# educationalBoard.net
KiCad netlist of a schematic drawn in Altium Designer
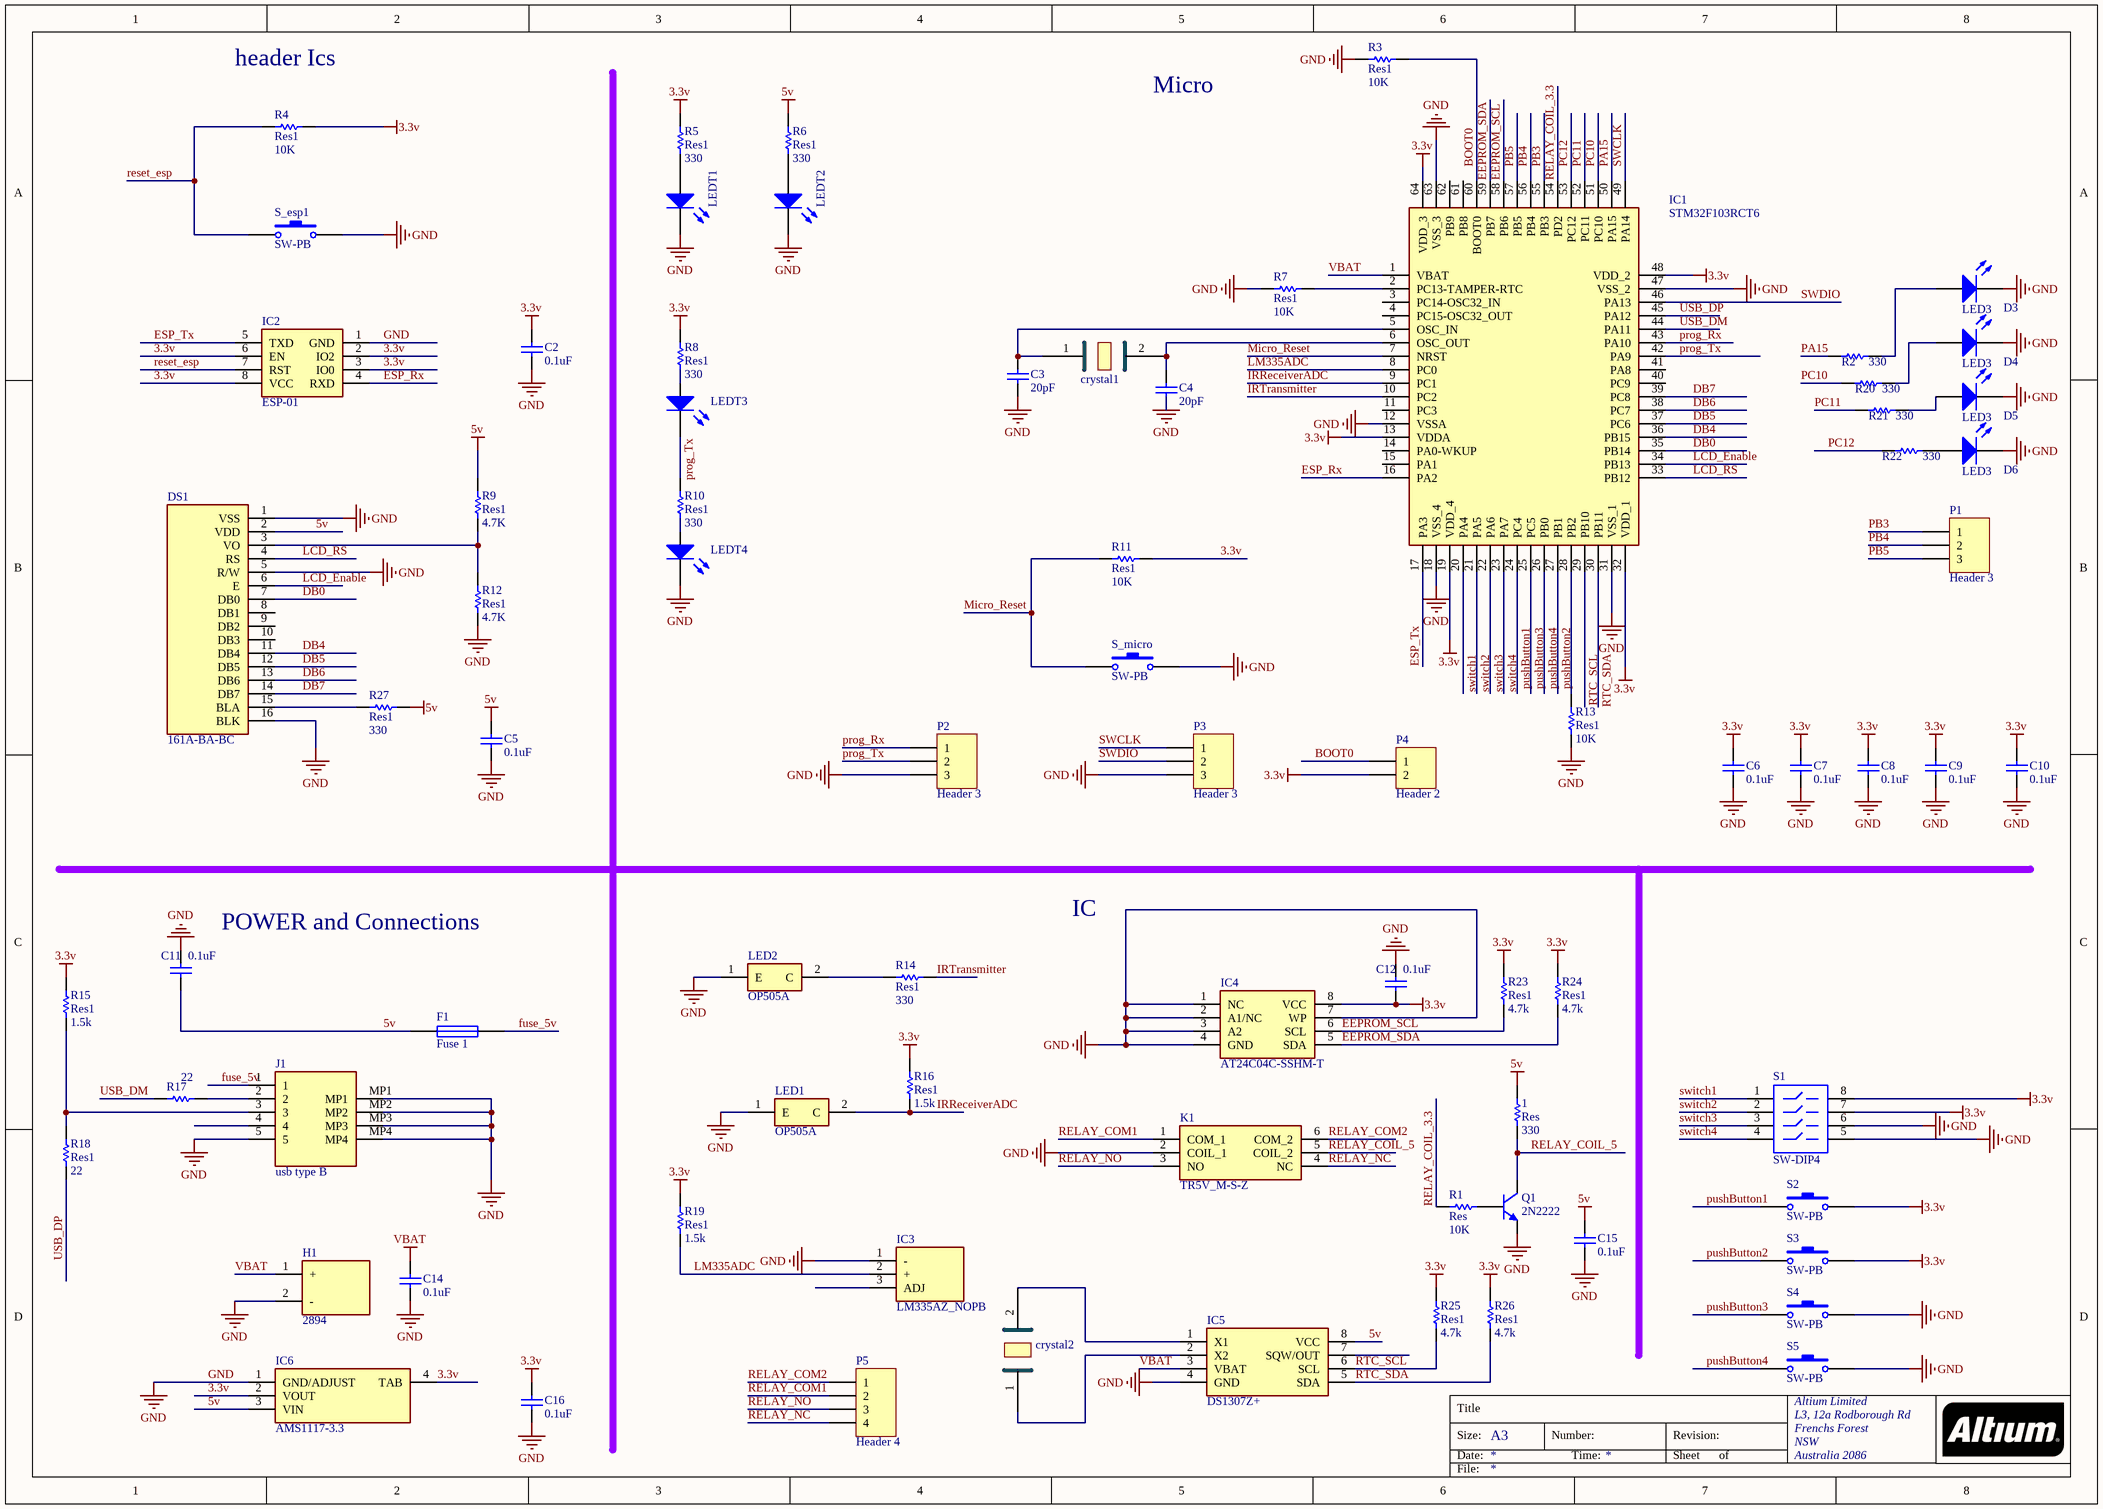
[diagram p0: educationalBoard.SchDoc]

(export (version "E")
  (design (tool "Eeschema 10.0.6"))
  (components
    (comp (ref "1")
      (value "Res")
      (footprint "J1-0603")
      (description "Semiconductor Resistor")
      (fields (field (name "ALTIUM_VALUE") "330") (field (name "PUBLISHER") "Altium Limited"))
      (libsource (lib "KN2CLib") (part "Res"))
    )
    (comp (ref "C2")
      (value "0.1uF")
      (footprint "J1-0603")
      (description "Ceramic Chip Capacitor - Standard")
      (fields (field (name "Comment") "C0603") (field (name "PUBLISHER") "Altium Limited"))
      (libsource (lib "KEMET Chip Capacitor") (part "C0603"))
    )
    (comp (ref "C3")
      (value "20pF")
      (footprint "J1-0603")
      (description "Ceramic Chip Capacitor - Standard")
      (fields (field (name "Comment") "C0603") (field (name "PUBLISHER") "Altium Limited"))
      (libsource (lib "KEMET Chip Capacitor") (part "C0603"))
    )
    (comp (ref "C4")
      (value "20pF")
      (footprint "J1-0603")
      (description "Ceramic Chip Capacitor - Standard")
      (fields (field (name "Comment") "C0603") (field (name "PUBLISHER") "Altium Limited"))
      (libsource (lib "KEMET Chip Capacitor") (part "C0603"))
    )
    (comp (ref "C5")
      (value "0.1uF")
      (footprint "J1-0603")
      (description "Ceramic Chip Capacitor - Standard")
      (fields (field (name "Comment") "C0603") (field (name "PUBLISHER") "Altium Limited"))
      (libsource (lib "KEMET Chip Capacitor") (part "C0603"))
    )
    (comp (ref "C6")
      (value "0.1uF")
      (footprint "J1-0603")
      (description "Ceramic Chip Capacitor - Standard")
      (fields (field (name "Comment") "C0603") (field (name "PUBLISHER") "Altium Limited"))
      (libsource (lib "KEMET Chip Capacitor") (part "C0603"))
    )
    (comp (ref "C7")
      (value "0.1uF")
      (footprint "J1-0603")
      (description "Ceramic Chip Capacitor - Standard")
      (fields (field (name "Comment") "C0603") (field (name "PUBLISHER") "Altium Limited"))
      (libsource (lib "KEMET Chip Capacitor") (part "C0603"))
    )
    (comp (ref "C8")
      (value "0.1uF")
      (footprint "J1-0603")
      (description "Ceramic Chip Capacitor - Standard")
      (fields (field (name "Comment") "C0603") (field (name "PUBLISHER") "Altium Limited"))
      (libsource (lib "KEMET Chip Capacitor") (part "C0603"))
    )
    (comp (ref "C9")
      (value "0.1uF")
      (footprint "J1-0603")
      (description "Ceramic Chip Capacitor - Standard")
      (fields (field (name "Comment") "C0603") (field (name "PUBLISHER") "Altium Limited"))
      (libsource (lib "KEMET Chip Capacitor") (part "C0603"))
    )
    (comp (ref "C10")
      (value "0.1uF")
      (footprint "J1-0603")
      (description "Ceramic Chip Capacitor - Standard")
      (fields (field (name "Comment") "C0603") (field (name "PUBLISHER") "Altium Limited"))
      (libsource (lib "KEMET Chip Capacitor") (part "C0603"))
    )
    (comp (ref "C11")
      (value "0.1uF")
      (footprint "J1-0603")
      (description "Ceramic Chip Capacitor - Standard")
      (fields (field (name "Comment") "C0603") (field (name "PUBLISHER") "Altium Limited"))
      (libsource (lib "KEMET Chip Capacitor") (part "C0603"))
    )
    (comp (ref "C12")
      (value "0.1uF")
      (footprint "J1-0603")
      (description "Ceramic Chip Capacitor - Standard")
      (fields (field (name "Comment") "C0603") (field (name "PUBLISHER") "Altium Limited"))
      (libsource (lib "KEMET Chip Capacitor") (part "C0603"))
    )
    (comp (ref "C14")
      (value "0.1uF")
      (footprint "J1-0603")
      (description "Ceramic Chip Capacitor - Standard")
      (fields (field (name "Comment") "C0603") (field (name "PUBLISHER") "Altium Limited"))
      (libsource (lib "KEMET Chip Capacitor") (part "C0603"))
    )
    (comp (ref "C15")
      (value "0.1uF")
      (footprint "J1-0603")
      (description "Ceramic Chip Capacitor - Standard")
      (fields (field (name "Comment") "C0603") (field (name "PUBLISHER") "Altium Limited"))
      (libsource (lib "KEMET Chip Capacitor") (part "C0603"))
    )
    (comp (ref "C16")
      (value "0.1uF")
      (footprint "J1-0603")
      (description "Ceramic Chip Capacitor - Standard")
      (fields (field (name "Comment") "C0603") (field (name "PUBLISHER") "Altium Limited"))
      (libsource (lib "KEMET Chip Capacitor") (part "C0603"))
    )
    (comp (ref "crystal1")
      (value "clockProducerDeep")
      (footprint "deep crystal")
      (libsource (lib "Schlib1") (part "deep crystal"))
    )
    (comp (ref "crystal2")
      (value "clockProducerDeep")
      (footprint "Deep Crystal small")
      (libsource (lib "") (part "deep crystal_1"))
    )
    (comp (ref "D3")
      (value "LED3")
      (footprint "3518")
      (description "Typical BLUE SiC LED")
      (fields (field (name "PUBLISHER") "Altium Limited"))
      (libsource (lib "Miscellaneous Devices") (part "LED3"))
    )
    (comp (ref "D4")
      (value "LED3")
      (footprint "3518")
      (description "Typical BLUE SiC LED")
      (fields (field (name "PUBLISHER") "Altium Limited"))
      (libsource (lib "Miscellaneous Devices") (part "LED3"))
    )
    (comp (ref "D5")
      (value "LED3")
      (footprint "3518")
      (description "Typical BLUE SiC LED")
      (fields (field (name "PUBLISHER") "Altium Limited"))
      (libsource (lib "Miscellaneous Devices") (part "LED3"))
    )
    (comp (ref "D6")
      (value "LED3")
      (footprint "3518")
      (description "Typical BLUE SiC LED")
      (fields (field (name "PUBLISHER") "Altium Limited"))
      (libsource (lib "Miscellaneous Devices") (part "LED3"))
    )
    (comp (ref "DS1")
      (value "161A-BA-BC")
      (footprint "Miscellaneous Connectors:HDR1X16")
      (description "Display")
      (libsource (lib "SamacSys") (part "161A-BA-BC"))
    )
    (comp (ref "F1")
      (value "Fuse 1")
      (footprint "0805")
      (description "Fuse")
      (fields (field (name "PUBLISHER") "Altium Limited"))
      (libsource (lib "Miscellaneous Devices") (part "Fuse 1"))
    )
    (comp (ref "H1")
      (value "2894")
      (footprint "SamacSys:2894")
      (description "Hardware")
      (fields (field (name "MOUSER PART NUMBER") "534-2894"))
      (libsource (lib "SamacSys") (part "2894"))
    )
    (comp (ref "IC1")
      (value "STM32F103RCT6")
      (footprint "SamacSys:QFP50P1200X1200X160-64N")
      (description "Integrated Circuit")
      (fields (field (name "MOUSER PART NUMBER") "511-STM32F103RCT6"))
      (libsource (lib "*") (part "STM32F103RCT6"))
    )
    (comp (ref "IC2")
      (value "ESP-01")
      (footprint "HDR2X4")
      (description "Integrated Circuit")
      (libsource (lib "*") (part "ESP-01"))
    )
    (comp (ref "IC3")
      (value "LM335AZ_NOPB")
      (footprint "HDR1X3")
      (description "Integrated Circuit")
      (fields
        (field (name "MANUFACTURER_PART_NUMBER") "LM335AZ/NOPB")
        (field (name "MOUSER PART NUMBER") "926-LM335AZ/NOPB")
      )
      (libsource (lib "*") (part "LM335AZ_NOPB"))
    )
    (comp (ref "IC4")
      (value "AT24C04C-SSHM-T")
      (footprint "SamacSys:SOIC127P600X175-8N")
      (description "Integrated Circuit")
      (fields (field (name "MOUSER PART NUMBER") "556-AT24C04C-SSHM-T"))
      (libsource (lib "*") (part "AT24C04C-SSHM-T"))
    )
    (comp (ref "IC5")
      (value "DS1307Z+")
      (footprint "SamacSys:SOIC127P600X175-8N")
      (description "Integrated Circuit")
      (fields (field (name "MOUSER PART NUMBER") "700-DS1307Z"))
      (libsource (lib "*") (part "DS1307Z+"))
    )
    (comp (ref "IC6")
      (value "AMS1117-3.3")
      (footprint "SamacSys:SOT229P700X180-4N")
      (description "Integrated Circuit")
      (fields (field (name "MANUFACTURER_PART_NUMBER") "AMS1117-1.5"))
      (libsource (lib "*") (part "AMS1117-1.5"))
    )
    (comp (ref "J1")
      (value "usb type B")
      (footprint "SamacSys:0474910001")
      (description "Connector")
      (fields (field (name "MANUFACTURER_PART_NUMBER") "0474910001"))
      (libsource (lib "SamacSys") (part "0474910001"))
    )
    (comp (ref "K1")
      (value "TR5V_M-S-Z")
      (footprint "SamacSys:TR5VMSZ")
      (description "Relay or Contactor")
      (fields (field (name "MANUFACTURER_PART_NUMBER") "TR5V M-S-Z"))
      (libsource (lib "*") (part "TR5V_M-S-Z"))
    )
    (comp (ref "LED1")
      (value "OP505A")
      (footprint "SamacSys:OP505A")
      (description "LED (Multiple)")
      (fields (field (name "MOUSER PART NUMBER") "828-OP505A"))
      (libsource (lib "SamacSys") (part "OP505A"))
    )
    (comp (ref "LED2")
      (value "OP505A")
      (footprint "SamacSys:OP505A")
      (description "LED (Multiple)")
      (fields (field (name "MOUSER PART NUMBER") "828-OP505A"))
      (libsource (lib "SamacSys") (part "OP505A"))
    )
    (comp (ref "LEDT1")
      (value "~")
      (footprint "3518")
      (description "Typical BLUE SiC LED")
      (fields (field (name "PUBLISHER") "Altium Limited"))
      (libsource (lib "Miscellaneous Devices") (part "LED3"))
    )
    (comp (ref "LEDT2")
      (value "~")
      (footprint "3518")
      (description "Typical BLUE SiC LED")
      (fields (field (name "PUBLISHER") "Altium Limited"))
      (libsource (lib "Miscellaneous Devices") (part "LED3"))
    )
    (comp (ref "LEDT3")
      (value "~")
      (footprint "3518")
      (description "Typical BLUE SiC LED")
      (fields (field (name "PUBLISHER") "Altium Limited"))
      (libsource (lib "Miscellaneous Devices") (part "LED3"))
    )
    (comp (ref "LEDT4")
      (value "~")
      (footprint "3518")
      (description "Typical BLUE SiC LED")
      (fields (field (name "PUBLISHER") "Altium Limited"))
      (libsource (lib "Miscellaneous Devices") (part "LED3"))
    )
    (comp (ref "P1")
      (value "Header 3")
      (footprint "HDR1X3")
      (description "Header, 3-Pin")
      (fields (field (name "PUBLISHER") "Altium Limited"))
      (libsource (lib "Miscellaneous Connectors") (part "Header 3"))
    )
    (comp (ref "P2")
      (value "Header 3")
      (footprint "HDR1X3")
      (description "Header, 3-Pin")
      (fields (field (name "PUBLISHER") "Altium Limited"))
      (libsource (lib "Miscellaneous Connectors") (part "Header 3"))
    )
    (comp (ref "P3")
      (value "Header 3")
      (footprint "HDR1X3")
      (description "Header, 3-Pin")
      (fields (field (name "PUBLISHER") "Altium Limited"))
      (libsource (lib "Miscellaneous Connectors") (part "Header 3"))
    )
    (comp (ref "P4")
      (value "Header 2")
      (footprint "HDR1X2")
      (description "Header, 2-Pin")
      (fields (field (name "PUBLISHER") "Altium Limited"))
      (libsource (lib "Miscellaneous Connectors") (part "Header 2"))
    )
    (comp (ref "P5")
      (value "Header 4")
      (footprint "HDR1X4")
      (description "Header, 4-Pin")
      (fields (field (name "PUBLISHER") "Altium Limited"))
      (libsource (lib "Miscellaneous Connectors") (part "Header 4"))
    )
    (comp (ref "Q1")
      (value "2N2222")
      (footprint "SOT-23")
      (description "NPN Bipolar Transistor")
      (fields (field (name "PUBLISHER") "Altium Limited"))
      (libsource (lib "KN2CLib") (part "2N2222"))
    )
    (comp (ref "R1")
      (value "Res")
      (footprint "J1-0603")
      (description "Semiconductor Resistor")
      (fields (field (name "ALTIUM_VALUE") "10K") (field (name "PUBLISHER") "Altium Limited"))
      (libsource (lib "KN2CLib") (part "Res"))
    )
    (comp (ref "R2")
      (value "330")
      (footprint "j1-0603")
      (description "Resistor")
      (fields (field (name "Comment") "Res1") (field (name "PUBLISHER") "Altium Limited"))
      (libsource (lib "Miscellaneous Devices") (part "Res1"))
    )
    (comp (ref "R3")
      (value "Res1")
      (footprint "J1-0603")
      (description "Resistor")
      (fields (field (name "ALTIUM_VALUE") "10K") (field (name "PUBLISHER") "Altium Limited"))
      (libsource (lib "Miscellaneous Devices") (part "Res1"))
    )
    (comp (ref "R4")
      (value "Res1")
      (footprint "J1-0603")
      (description "Resistor")
      (fields (field (name "ALTIUM_VALUE") "10K") (field (name "PUBLISHER") "Altium Limited"))
      (libsource (lib "Miscellaneous Devices") (part "Res1"))
    )
    (comp (ref "R5")
      (value "Res1")
      (footprint "j1-0603")
      (description "Resistor")
      (fields (field (name "ALTIUM_VALUE") "330") (field (name "PUBLISHER") "Altium Limited"))
      (libsource (lib "Miscellaneous Devices") (part "Res1"))
    )
    (comp (ref "R6")
      (value "Res1")
      (footprint "j1-0603")
      (description "Resistor")
      (fields (field (name "ALTIUM_VALUE") "330") (field (name "PUBLISHER") "Altium Limited"))
      (libsource (lib "Miscellaneous Devices") (part "Res1"))
    )
    (comp (ref "R7")
      (value "Res1")
      (footprint "J1-0603")
      (description "Resistor")
      (fields (field (name "ALTIUM_VALUE") "10K") (field (name "PUBLISHER") "Altium Limited"))
      (libsource (lib "Miscellaneous Devices") (part "Res1"))
    )
    (comp (ref "R8")
      (value "Res1")
      (footprint "j1-0603")
      (description "Resistor")
      (fields (field (name "ALTIUM_VALUE") "330") (field (name "PUBLISHER") "Altium Limited"))
      (libsource (lib "Miscellaneous Devices") (part "Res1"))
    )
    (comp (ref "R9")
      (value "Res1")
      (footprint "J1-0603")
      (description "Resistor")
      (fields (field (name "ALTIUM_VALUE") "4.7K") (field (name "PUBLISHER") "Altium Limited"))
      (libsource (lib "Miscellaneous Devices") (part "Res1"))
    )
    (comp (ref "R10")
      (value "Res1")
      (footprint "j1-0603")
      (description "Resistor")
      (fields (field (name "ALTIUM_VALUE") "330") (field (name "PUBLISHER") "Altium Limited"))
      (libsource (lib "Miscellaneous Devices") (part "Res1"))
    )
    (comp (ref "R11")
      (value "Res1")
      (footprint "J1-0603")
      (description "Resistor")
      (fields (field (name "ALTIUM_VALUE") "10K") (field (name "PUBLISHER") "Altium Limited"))
      (libsource (lib "Miscellaneous Devices") (part "Res1"))
    )
    (comp (ref "R12")
      (value "Res1")
      (footprint "J1-0603")
      (description "Resistor")
      (fields (field (name "ALTIUM_VALUE") "4.7K") (field (name "PUBLISHER") "Altium Limited"))
      (libsource (lib "Miscellaneous Devices") (part "Res1"))
    )
    (comp (ref "R13")
      (value "Res1")
      (footprint "J1-0603")
      (description "Resistor")
      (fields (field (name "ALTIUM_VALUE") "10K") (field (name "PUBLISHER") "Altium Limited"))
      (libsource (lib "Miscellaneous Devices") (part "Res1"))
    )
    (comp (ref "R14")
      (value "Res1")
      (footprint "J1-0603")
      (description "Resistor")
      (fields (field (name "ALTIUM_VALUE") "330") (field (name "PUBLISHER") "Altium Limited"))
      (libsource (lib "Miscellaneous Devices") (part "Res1"))
    )
    (comp (ref "R15")
      (value "Res1")
      (footprint "J1-0603")
      (description "Resistor")
      (fields (field (name "ALTIUM_VALUE") "1.5k") (field (name "PUBLISHER") "Altium Limited"))
      (libsource (lib "Miscellaneous Devices") (part "Res1"))
    )
    (comp (ref "R16")
      (value "Res1")
      (footprint "J1-0603")
      (description "Resistor")
      (fields (field (name "ALTIUM_VALUE") "1.5k") (field (name "PUBLISHER") "Altium Limited"))
      (libsource (lib "Miscellaneous Devices") (part "Res1"))
    )
    (comp (ref "R17")
      (value "22")
      (footprint "J1-0603")
      (description "Resistor")
      (fields (field (name "Comment") "Res1") (field (name "PUBLISHER") "Altium Limited"))
      (libsource (lib "Miscellaneous Devices") (part "Res1"))
    )
    (comp (ref "R18")
      (value "Res1")
      (footprint "J1-0603")
      (description "Resistor")
      (fields (field (name "ALTIUM_VALUE") "22") (field (name "PUBLISHER") "Altium Limited"))
      (libsource (lib "Miscellaneous Devices") (part "Res1"))
    )
    (comp (ref "R19")
      (value "Res1")
      (footprint "J1-0603")
      (description "Resistor")
      (fields (field (name "ALTIUM_VALUE") "1.5k") (field (name "PUBLISHER") "Altium Limited"))
      (libsource (lib "Miscellaneous Devices") (part "Res1"))
    )
    (comp (ref "R20")
      (value "330")
      (footprint "j1-0603")
      (description "Resistor")
      (fields (field (name "Comment") "Res1") (field (name "PUBLISHER") "Altium Limited"))
      (libsource (lib "Miscellaneous Devices") (part "Res1"))
    )
    (comp (ref "R21")
      (value "330")
      (footprint "j1-0603")
      (description "Resistor")
      (fields (field (name "Comment") "Res1") (field (name "PUBLISHER") "Altium Limited"))
      (libsource (lib "Miscellaneous Devices") (part "Res1"))
    )
    (comp (ref "R22")
      (value "330")
      (footprint "j1-0603")
      (description "Resistor")
      (fields (field (name "Comment") "Res1") (field (name "PUBLISHER") "Altium Limited"))
      (libsource (lib "Miscellaneous Devices") (part "Res1"))
    )
    (comp (ref "R23")
      (value "Res1")
      (footprint "J1-0603")
      (description "Resistor")
      (fields (field (name "ALTIUM_VALUE") "4.7k") (field (name "PUBLISHER") "Altium Limited"))
      (libsource (lib "Miscellaneous Devices") (part "Res1"))
    )
    (comp (ref "R24")
      (value "Res1")
      (footprint "J1-0603")
      (description "Resistor")
      (fields (field (name "ALTIUM_VALUE") "4.7k") (field (name "PUBLISHER") "Altium Limited"))
      (libsource (lib "Miscellaneous Devices") (part "Res1"))
    )
    (comp (ref "R25")
      (value "Res1")
      (footprint "J1-0603")
      (description "Resistor")
      (fields (field (name "ALTIUM_VALUE") "4.7k") (field (name "PUBLISHER") "Altium Limited"))
      (libsource (lib "Miscellaneous Devices") (part "Res1"))
    )
    (comp (ref "R26")
      (value "Res1")
      (footprint "J1-0603")
      (description "Resistor")
      (fields (field (name "ALTIUM_VALUE") "4.7k") (field (name "PUBLISHER") "Altium Limited"))
      (libsource (lib "Miscellaneous Devices") (part "Res1"))
    )
    (comp (ref "R27")
      (value "Res1")
      (footprint "J1-0603")
      (description "Resistor")
      (fields (field (name "ALTIUM_VALUE") "330") (field (name "PUBLISHER") "Altium Limited"))
      (libsource (lib "Miscellaneous Devices") (part "Res1"))
    )
    (comp (ref "S1")
      (value "SW-DIP4")
      (footprint "DIP-8")
      (description "DIP Switch")
      (fields (field (name "PUBLISHER") "Altium Limited"))
      (libsource (lib "Miscellaneous Devices") (part "SW-DIP4"))
    )
    (comp (ref "S2")
      (value "SW-PB")
      (footprint "button")
      (description "Switch")
      (fields (field (name "PUBLISHER") "Altium Limited"))
      (libsource (lib "Miscellaneous Devices") (part "SW-PB"))
    )
    (comp (ref "S3")
      (value "SW-PB")
      (footprint "button")
      (description "Switch")
      (fields (field (name "PUBLISHER") "Altium Limited"))
      (libsource (lib "Miscellaneous Devices") (part "SW-PB"))
    )
    (comp (ref "S4")
      (value "SW-PB")
      (footprint "button")
      (description "Switch")
      (fields (field (name "PUBLISHER") "Altium Limited"))
      (libsource (lib "Miscellaneous Devices") (part "SW-PB"))
    )
    (comp (ref "S5")
      (value "SW-PB")
      (footprint "button")
      (description "Switch")
      (fields (field (name "PUBLISHER") "Altium Limited"))
      (libsource (lib "Miscellaneous Devices") (part "SW-PB"))
    )
    (comp (ref "S_esp1")
      (value "SW-PB")
      (footprint "button")
      (description "Switch")
      (fields (field (name "PUBLISHER") "Altium Limited"))
      (libsource (lib "Miscellaneous Devices") (part "SW-PB"))
    )
    (comp (ref "S_micro")
      (value "SW-PB")
      (footprint "button")
      (description "Switch")
      (fields (field (name "PUBLISHER") "Altium Limited"))
      (libsource (lib "Miscellaneous Devices") (part "SW-PB"))
    )
  )
  (nets
    (net (code "1") (name "/BOOT0") (class "Default")
      (node (ref "IC1") (pin "60") (pinfunction "BOOT0_60") (pintype "passive"))
      (node (ref "P4") (pin "1") (pinfunction "1_1") (pintype "passive"))
      (node (ref "R3") (pin "1") (pinfunction "1_1") (pintype "passive"))
    )
    (net (code "2") (name "/DB0") (class "Default")
      (node (ref "DS1") (pin "7") (pinfunction "DB0_7") (pintype "passive"))
      (node (ref "IC1") (pin "35") (pinfunction "PB14_35") (pintype "passive"))
    )
    (net (code "3") (name "/DB4") (class "Default")
      (node (ref "DS1") (pin "11") (pinfunction "DB4_11") (pintype "passive"))
      (node (ref "IC1") (pin "36") (pinfunction "PB15_36") (pintype "passive"))
    )
    (net (code "4") (name "/DB5") (class "Default")
      (node (ref "DS1") (pin "12") (pinfunction "DB5_12") (pintype "passive"))
      (node (ref "IC1") (pin "37") (pinfunction "PC6_37") (pintype "passive"))
    )
    (net (code "5") (name "/DB6") (class "Default")
      (node (ref "DS1") (pin "13") (pinfunction "DB6_13") (pintype "passive"))
      (node (ref "IC1") (pin "38") (pinfunction "PC7_38") (pintype "passive"))
    )
    (net (code "6") (name "/DB7") (class "Default")
      (node (ref "DS1") (pin "14") (pinfunction "DB7_14") (pintype "passive"))
      (node (ref "IC1") (pin "39") (pinfunction "PC8_39") (pintype "passive"))
    )
    (net (code "7") (name "/EEPROM_SCL") (class "Default")
      (node (ref "IC1") (pin "58") (pinfunction "PB6_58") (pintype "passive"))
      (node (ref "IC4") (pin "6") (pinfunction "SCL_6") (pintype "passive"))
      (node (ref "R23") (pin "2") (pinfunction "2_2") (pintype "passive"))
    )
    (net (code "8") (name "/EEPROM_SDA") (class "Default")
      (node (ref "IC1") (pin "59") (pinfunction "PB7_59") (pintype "passive"))
      (node (ref "IC4") (pin "5") (pinfunction "SDA_5") (pintype "passive"))
      (node (ref "R24") (pin "2") (pinfunction "2_2") (pintype "passive"))
    )
    (net (code "9") (name "/ESP_Rx") (class "Default")
      (node (ref "IC1") (pin "16") (pinfunction "PA2_16") (pintype "passive"))
      (node (ref "IC2") (pin "4") (pinfunction "RXD_4") (pintype "passive"))
    )
    (net (code "10") (name "/ESP_Tx") (class "Default")
      (node (ref "IC1") (pin "17") (pinfunction "PA3_17") (pintype "passive"))
      (node (ref "IC2") (pin "5") (pinfunction "TXD_5") (pintype "passive"))
    )
    (net (code "11") (name "/IRReceiverADC") (class "Default")
      (node (ref "IC1") (pin "9") (pinfunction "PC1_9") (pintype "passive"))
      (node (ref "LED1") (pin "2") (pinfunction "C_2") (pintype "passive"))
      (node (ref "R16") (pin "2") (pinfunction "2_2") (pintype "passive"))
    )
    (net (code "12") (name "/IRTransmitter") (class "Default")
      (node (ref "IC1") (pin "10") (pinfunction "PC2_10") (pintype "passive"))
      (node (ref "R14") (pin "1") (pinfunction "1_1") (pintype "passive"))
    )
    (net (code "13") (name "/LCD_Enable") (class "Default")
      (node (ref "DS1") (pin "6") (pinfunction "E_6") (pintype "passive"))
      (node (ref "IC1") (pin "34") (pinfunction "PB13_34") (pintype "passive"))
    )
    (net (code "14") (name "/LCD_RS") (class "Default")
      (node (ref "DS1") (pin "4") (pinfunction "RS_4") (pintype "passive"))
      (node (ref "IC1") (pin "33") (pinfunction "PB12_33") (pintype "passive"))
    )
    (net (code "15") (name "/LM335ADC") (class "Default")
      (node (ref "IC1") (pin "8") (pinfunction "PC0_8") (pintype "passive"))
      (node (ref "IC3") (pin "2") (pinfunction "+_2") (pintype "passive"))
      (node (ref "R19") (pin "1") (pinfunction "1_1") (pintype "passive"))
    )
    (net (code "16") (name "/Micro_Reset") (class "Default")
      (node (ref "IC1") (pin "7") (pinfunction "NRST_7") (pintype "passive"))
      (node (ref "R11") (pin "1") (pinfunction "1_1") (pintype "passive"))
      (node (ref "S_micro") (pin "1") (pinfunction "1_1") (pintype "passive"))
    )
    (net (code "17") (name "/PA15") (class "Default")
      (node (ref "IC1") (pin "50") (pinfunction "PA15_50") (pintype "passive"))
      (node (ref "R2") (pin "2") (pinfunction "2_2") (pintype "passive"))
    )
    (net (code "18") (name "/PB3") (class "Default")
      (node (ref "IC1") (pin "55") (pinfunction "PB3_55") (pintype "passive"))
      (node (ref "P1") (pin "1") (pinfunction "1_1") (pintype "passive"))
    )
    (net (code "19") (name "/PB4") (class "Default")
      (node (ref "IC1") (pin "56") (pinfunction "PB4_56") (pintype "passive"))
      (node (ref "P1") (pin "2") (pinfunction "2_2") (pintype "passive"))
    )
    (net (code "20") (name "/PB5") (class "Default")
      (node (ref "IC1") (pin "57") (pinfunction "PB5_57") (pintype "passive"))
      (node (ref "P1") (pin "3") (pinfunction "3_3") (pintype "passive"))
    )
    (net (code "21") (name "/PC10") (class "Default")
      (node (ref "IC1") (pin "51") (pinfunction "PC10_51") (pintype "passive"))
      (node (ref "R20") (pin "1") (pinfunction "1_1") (pintype "passive"))
    )
    (net (code "22") (name "/PC11") (class "Default")
      (node (ref "IC1") (pin "52") (pinfunction "PC11_52") (pintype "passive"))
      (node (ref "R21") (pin "1") (pinfunction "1_1") (pintype "passive"))
    )
    (net (code "23") (name "/PC12") (class "Default")
      (node (ref "IC1") (pin "53") (pinfunction "PC12_53") (pintype "passive"))
      (node (ref "R22") (pin "1") (pinfunction "1_1") (pintype "passive"))
    )
    (net (code "24") (name "/RELAY_COIL_3.3") (class "Default")
      (node (ref "IC1") (pin "54") (pinfunction "PD2_54") (pintype "passive"))
      (node (ref "R1") (pin "1") (pinfunction "1_1") (pintype "passive"))
    )
    (net (code "25") (name "/RELAY_COIL_5") (class "Default")
      (node (ref "1") (pin "1") (pinfunction "1_1") (pintype "passive"))
      (node (ref "K1") (pin "5") (pinfunction "COIL_2_5") (pintype "passive"))
      (node (ref "Q1") (pin "1") (pinfunction "C_1") (pintype "passive"))
    )
    (net (code "26") (name "/RELAY_COM1") (class "Default")
      (node (ref "K1") (pin "1") (pinfunction "COM_1_1") (pintype "passive"))
      (node (ref "P5") (pin "2") (pinfunction "2_2") (pintype "passive"))
    )
    (net (code "27") (name "/RELAY_COM2") (class "Default")
      (node (ref "K1") (pin "6") (pinfunction "COM_2_6") (pintype "passive"))
      (node (ref "P5") (pin "1") (pinfunction "1_1") (pintype "passive"))
    )
    (net (code "28") (name "/RELAY_NC") (class "Default")
      (node (ref "K1") (pin "4") (pinfunction "NC_4") (pintype "passive"))
      (node (ref "P5") (pin "4") (pinfunction "4_4") (pintype "passive"))
    )
    (net (code "29") (name "/RELAY_NO") (class "Default")
      (node (ref "K1") (pin "3") (pinfunction "NO_3") (pintype "passive"))
      (node (ref "P5") (pin "3") (pinfunction "3_3") (pintype "passive"))
    )
    (net (code "30") (name "/RTC_SCL") (class "Default")
      (node (ref "IC1") (pin "29") (pinfunction "PB10_29") (pintype "passive"))
      (node (ref "IC5") (pin "6") (pinfunction "SCL_6") (pintype "passive"))
      (node (ref "R25") (pin "2") (pinfunction "2_2") (pintype "passive"))
    )
    (net (code "31") (name "/RTC_SDA") (class "Default")
      (node (ref "IC1") (pin "30") (pinfunction "PB11_30") (pintype "passive"))
      (node (ref "IC5") (pin "5") (pinfunction "SDA_5") (pintype "passive"))
      (node (ref "R26") (pin "2") (pinfunction "2_2") (pintype "passive"))
    )
    (net (code "32") (name "/SWCLK") (class "Default")
      (node (ref "IC1") (pin "49") (pinfunction "PA14_49") (pintype "passive"))
      (node (ref "P3") (pin "1") (pinfunction "1_1") (pintype "passive"))
    )
    (net (code "33") (name "/SWDIO") (class "Default")
      (node (ref "IC1") (pin "46") (pinfunction "PA13_46") (pintype "passive"))
      (node (ref "P3") (pin "2") (pinfunction "2_2") (pintype "passive"))
    )
    (net (code "34") (name "/USB_DM") (class "Default")
      (node (ref "IC1") (pin "44") (pinfunction "PA11_44") (pintype "passive"))
      (node (ref "R17") (pin "2") (pinfunction "2_2") (pintype "passive"))
    )
    (net (code "35") (name "/USB_DP") (class "Default")
      (node (ref "IC1") (pin "45") (pinfunction "PA12_45") (pintype "passive"))
      (node (ref "R18") (pin "2") (pinfunction "2_2") (pintype "passive"))
    )
    (net (code "36") (name "/fuse_5v") (class "Default")
      (node (ref "F1") (pin "2") (pinfunction "2_2") (pintype "passive"))
      (node (ref "J1") (pin "1") (pinfunction "1_1") (pintype "passive"))
    )
    (net (code "37") (name "/prog_Rx") (class "Default")
      (node (ref "IC1") (pin "43") (pinfunction "PA10_43") (pintype "passive"))
      (node (ref "P2") (pin "1") (pinfunction "1_1") (pintype "passive"))
    )
    (net (code "38") (name "/prog_Tx") (class "Default")
      (node (ref "IC1") (pin "42") (pinfunction "PA9_42") (pintype "passive"))
      (node (ref "LEDT3") (pin "2") (pinfunction "K_2") (pintype "passive"))
      (node (ref "P2") (pin "2") (pinfunction "2_2") (pintype "passive"))
      (node (ref "R10") (pin "1") (pinfunction "1_1") (pintype "passive"))
    )
    (net (code "39") (name "/pushButton1") (class "Default")
      (node (ref "IC1") (pin "24") (pinfunction "PC4_24") (pintype "passive"))
      (node (ref "S2") (pin "1") (pinfunction "1_1") (pintype "passive"))
    )
    (net (code "40") (name "/pushButton2") (class "Default")
      (node (ref "IC1") (pin "27") (pinfunction "PB1_27") (pintype "passive"))
      (node (ref "S3") (pin "1") (pinfunction "1_1") (pintype "passive"))
    )
    (net (code "41") (name "/pushButton3") (class "Default")
      (node (ref "IC1") (pin "25") (pinfunction "PC5_25") (pintype "passive"))
      (node (ref "S4") (pin "1") (pinfunction "1_1") (pintype "passive"))
    )
    (net (code "42") (name "/pushButton4") (class "Default")
      (node (ref "IC1") (pin "26") (pinfunction "PB0_26") (pintype "passive"))
      (node (ref "S5") (pin "1") (pinfunction "1_1") (pintype "passive"))
    )
    (net (code "43") (name "/reset_esp") (class "Default")
      (node (ref "IC2") (pin "7") (pinfunction "RST_7") (pintype "passive"))
      (node (ref "R4") (pin "1") (pinfunction "1_1") (pintype "passive"))
      (node (ref "S_esp1") (pin "1") (pinfunction "1_1") (pintype "passive"))
    )
    (net (code "44") (name "/switch1") (class "Default")
      (node (ref "IC1") (pin "20") (pinfunction "PA4_20") (pintype "passive"))
      (node (ref "S1") (pin "1") (pinfunction "1_1") (pintype "passive"))
    )
    (net (code "45") (name "/switch2") (class "Default")
      (node (ref "IC1") (pin "21") (pinfunction "PA5_21") (pintype "passive"))
      (node (ref "S1") (pin "2") (pinfunction "2_2") (pintype "passive"))
    )
    (net (code "46") (name "/switch3") (class "Default")
      (node (ref "IC1") (pin "22") (pinfunction "PA6_22") (pintype "passive"))
      (node (ref "S1") (pin "3") (pinfunction "3_3") (pintype "passive"))
    )
    (net (code "47") (name "/switch4") (class "Default")
      (node (ref "IC1") (pin "23") (pinfunction "PA7_23") (pintype "passive"))
      (node (ref "S1") (pin "4") (pinfunction "4_4") (pintype "passive"))
    )
    (net (code "48") (name "3.3v") (class "Default")
      (node (ref "C10") (pin "1") (pinfunction "1_1") (pintype "passive"))
      (node (ref "C12") (pin "1") (pinfunction "1_1") (pintype "passive"))
      (node (ref "C16") (pin "1") (pinfunction "1_1") (pintype "passive"))
      (node (ref "C2") (pin "1") (pinfunction "1_1") (pintype "passive"))
      (node (ref "C6") (pin "1") (pinfunction "1_1") (pintype "passive"))
      (node (ref "C7") (pin "1") (pinfunction "1_1") (pintype "passive"))
      (node (ref "C8") (pin "1") (pinfunction "1_1") (pintype "passive"))
      (node (ref "C9") (pin "1") (pinfunction "1_1") (pintype "passive"))
      (node (ref "IC1") (pin "13") (pinfunction "VDDA_13") (pintype "passive"))
      (node (ref "IC1") (pin "19") (pinfunction "VDD_4_19") (pintype "passive"))
      (node (ref "IC1") (pin "32") (pinfunction "VDD_1_32") (pintype "passive"))
      (node (ref "IC1") (pin "48") (pinfunction "VDD_2_48") (pintype "passive"))
      (node (ref "IC1") (pin "64") (pinfunction "VDD_3_64") (pintype "passive"))
      (node (ref "IC2") (pin "2") (pinfunction "IO2_2") (pintype "passive"))
      (node (ref "IC2") (pin "3") (pinfunction "IO0_3") (pintype "passive"))
      (node (ref "IC2") (pin "6") (pinfunction "EN_6") (pintype "passive"))
      (node (ref "IC2") (pin "8") (pinfunction "VCC_8") (pintype "passive"))
      (node (ref "IC4") (pin "8") (pinfunction "VCC_8") (pintype "passive"))
      (node (ref "IC6") (pin "2") (pinfunction "VOUT_2") (pintype "passive"))
      (node (ref "IC6") (pin "4") (pinfunction "TAB_4") (pintype "passive"))
      (node (ref "P4") (pin "2") (pinfunction "2_2") (pintype "passive"))
      (node (ref "R11") (pin "2") (pinfunction "2_2") (pintype "passive"))
      (node (ref "R15") (pin "2") (pinfunction "2_2") (pintype "passive"))
      (node (ref "R16") (pin "1") (pinfunction "1_1") (pintype "passive"))
      (node (ref "R19") (pin "2") (pinfunction "2_2") (pintype "passive"))
      (node (ref "R23") (pin "1") (pinfunction "1_1") (pintype "passive"))
      (node (ref "R24") (pin "1") (pinfunction "1_1") (pintype "passive"))
      (node (ref "R25") (pin "1") (pinfunction "1_1") (pintype "passive"))
      (node (ref "R26") (pin "1") (pinfunction "1_1") (pintype "passive"))
      (node (ref "R4") (pin "2") (pinfunction "2_2") (pintype "passive"))
      (node (ref "R5") (pin "1") (pinfunction "1_1") (pintype "passive"))
      (node (ref "R8") (pin "1") (pinfunction "1_1") (pintype "passive"))
      (node (ref "S1") (pin "7") (pinfunction "7_7") (pintype "passive"))
      (node (ref "S1") (pin "8") (pinfunction "8_8") (pintype "passive"))
      (node (ref "S2") (pin "2") (pinfunction "2_2") (pintype "passive"))
      (node (ref "S3") (pin "2") (pinfunction "2_2") (pintype "passive"))
    )
    (net (code "49") (name "5v") (class "Default")
      (node (ref "1") (pin "2") (pinfunction "2_2") (pintype "passive"))
      (node (ref "C11") (pin "1") (pinfunction "1_1") (pintype "passive"))
      (node (ref "C15") (pin "1") (pinfunction "1_1") (pintype "passive"))
      (node (ref "C5") (pin "1") (pinfunction "1_1") (pintype "passive"))
      (node (ref "DS1") (pin "2") (pinfunction "VDD_2") (pintype "passive"))
      (node (ref "F1") (pin "1") (pinfunction "1_1") (pintype "passive"))
      (node (ref "IC5") (pin "8") (pinfunction "VCC_8") (pintype "passive"))
      (node (ref "IC6") (pin "3") (pinfunction "VIN_3") (pintype "passive"))
      (node (ref "R27") (pin "1") (pinfunction "1_1") (pintype "passive"))
      (node (ref "R6") (pin "1") (pinfunction "1_1") (pintype "passive"))
      (node (ref "R9") (pin "2") (pinfunction "2_2") (pintype "passive"))
    )
    (net (code "50") (name "GND") (class "Default")
      (node (ref "C10") (pin "2") (pinfunction "2_2") (pintype "passive"))
      (node (ref "C11") (pin "2") (pinfunction "2_2") (pintype "passive"))
      (node (ref "C12") (pin "2") (pinfunction "2_2") (pintype "passive"))
      (node (ref "C14") (pin "2") (pinfunction "2_2") (pintype "passive"))
      (node (ref "C15") (pin "2") (pinfunction "2_2") (pintype "passive"))
      (node (ref "C16") (pin "2") (pinfunction "2_2") (pintype "passive"))
      (node (ref "C2") (pin "2") (pinfunction "2_2") (pintype "passive"))
      (node (ref "C3") (pin "1") (pinfunction "1_1") (pintype "passive"))
      (node (ref "C4") (pin "1") (pinfunction "1_1") (pintype "passive"))
      (node (ref "C5") (pin "2") (pinfunction "2_2") (pintype "passive"))
      (node (ref "C6") (pin "2") (pinfunction "2_2") (pintype "passive"))
      (node (ref "C7") (pin "2") (pinfunction "2_2") (pintype "passive"))
      (node (ref "C8") (pin "2") (pinfunction "2_2") (pintype "passive"))
      (node (ref "C9") (pin "2") (pinfunction "2_2") (pintype "passive"))
      (node (ref "D3") (pin "2") (pinfunction "K_2") (pintype "passive"))
      (node (ref "D4") (pin "2") (pinfunction "K_2") (pintype "passive"))
      (node (ref "D5") (pin "2") (pinfunction "K_2") (pintype "passive"))
      (node (ref "D6") (pin "2") (pinfunction "K_2") (pintype "passive"))
      (node (ref "DS1") (pin "1") (pinfunction "VSS_1") (pintype "passive"))
      (node (ref "DS1") (pin "16") (pinfunction "BLK_16") (pintype "passive"))
      (node (ref "DS1") (pin "5") (pinfunction "R/W_5") (pintype "passive"))
      (node (ref "H1") (pin "2") (pinfunction "-_2") (pintype "passive"))
      (node (ref "IC1") (pin "12") (pinfunction "VSSA_12") (pintype "passive"))
      (node (ref "IC1") (pin "18") (pinfunction "VSS_4_18") (pintype "passive"))
      (node (ref "IC1") (pin "31") (pinfunction "VSS_1_31") (pintype "passive"))
      (node (ref "IC1") (pin "47") (pinfunction "VSS_2_47") (pintype "passive"))
      (node (ref "IC1") (pin "63") (pinfunction "VSS_3_63") (pintype "passive"))
      (node (ref "IC2") (pin "1") (pinfunction "GND_1") (pintype "passive"))
      (node (ref "IC3") (pin "1") (pinfunction "-_1") (pintype "passive"))
      (node (ref "IC4") (pin "1") (pinfunction "NC_1") (pintype "passive"))
      (node (ref "IC4") (pin "2") (pinfunction "A1/NC_2") (pintype "passive"))
      (node (ref "IC4") (pin "3") (pinfunction "A2_3") (pintype "passive"))
      (node (ref "IC4") (pin "4") (pinfunction "GND_4") (pintype "passive"))
      (node (ref "IC4") (pin "7") (pinfunction "WP_7") (pintype "passive"))
      (node (ref "IC5") (pin "4") (pinfunction "GND_4") (pintype "passive"))
      (node (ref "IC6") (pin "1") (pinfunction "GND/ADJUST_1") (pintype "passive"))
      (node (ref "J1") (pin "5") (pinfunction "5_5") (pintype "passive"))
      (node (ref "J1") (pin "MP1") (pinfunction "MP1_MP1") (pintype "passive"))
      (node (ref "J1") (pin "MP2") (pinfunction "MP2_MP2") (pintype "passive"))
      (node (ref "J1") (pin "MP3") (pinfunction "MP3_MP3") (pintype "passive"))
      (node (ref "J1") (pin "MP4") (pinfunction "MP4_MP4") (pintype "passive"))
      (node (ref "K1") (pin "2") (pinfunction "COIL_1_2") (pintype "passive"))
      (node (ref "LED1") (pin "1") (pinfunction "E_1") (pintype "passive"))
      (node (ref "LED2") (pin "1") (pinfunction "E_1") (pintype "passive"))
      (node (ref "LEDT1") (pin "2") (pinfunction "K_2") (pintype "passive"))
      (node (ref "LEDT2") (pin "2") (pinfunction "K_2") (pintype "passive"))
      (node (ref "LEDT4") (pin "2") (pinfunction "K_2") (pintype "passive"))
      (node (ref "P2") (pin "3") (pinfunction "3_3") (pintype "passive"))
      (node (ref "P3") (pin "3") (pinfunction "3_3") (pintype "passive"))
      (node (ref "Q1") (pin "3") (pinfunction "E_3") (pintype "passive"))
      (node (ref "R12") (pin "1") (pinfunction "1_1") (pintype "passive"))
      (node (ref "R13") (pin "2") (pinfunction "2_2") (pintype "passive"))
      (node (ref "R3") (pin "2") (pinfunction "2_2") (pintype "passive"))
      (node (ref "R7") (pin "1") (pinfunction "1_1") (pintype "passive"))
      (node (ref "S1") (pin "5") (pinfunction "5_5") (pintype "passive"))
      (node (ref "S1") (pin "6") (pinfunction "6_6") (pintype "passive"))
      (node (ref "S4") (pin "2") (pinfunction "2_2") (pintype "passive"))
      (node (ref "S5") (pin "2") (pinfunction "2_2") (pintype "passive"))
      (node (ref "S_esp1") (pin "2") (pinfunction "2_2") (pintype "passive"))
      (node (ref "S_micro") (pin "2") (pinfunction "2_2") (pintype "passive"))
    )
    (net (code "51") (name "Net-(D3-A)") (class "Default")
      (node (ref "D3") (pin "1") (pinfunction "A_1") (pintype "passive"))
      (node (ref "R2") (pin "1") (pinfunction "1_1") (pintype "passive"))
    )
    (net (code "52") (name "Net-(D4-A)") (class "Default")
      (node (ref "D4") (pin "1") (pinfunction "A_1") (pintype "passive"))
      (node (ref "R20") (pin "2") (pinfunction "2_2") (pintype "passive"))
    )
    (net (code "53") (name "Net-(D5-A)") (class "Default")
      (node (ref "D5") (pin "1") (pinfunction "A_1") (pintype "passive"))
      (node (ref "R21") (pin "2") (pinfunction "2_2") (pintype "passive"))
    )
    (net (code "54") (name "Net-(D6-A)") (class "Default")
      (node (ref "D6") (pin "1") (pinfunction "A_1") (pintype "passive"))
      (node (ref "R22") (pin "2") (pinfunction "2_2") (pintype "passive"))
    )
    (net (code "55") (name "Net-(DS1-BLA)") (class "Default")
      (node (ref "DS1") (pin "15") (pinfunction "BLA_15") (pintype "passive"))
      (node (ref "R27") (pin "2") (pinfunction "2_2") (pintype "passive"))
    )
    (net (code "56") (name "Net-(DS1-VO)") (class "Default")
      (node (ref "DS1") (pin "3") (pinfunction "VO_3") (pintype "passive"))
      (node (ref "R12") (pin "2") (pinfunction "2_2") (pintype "passive"))
      (node (ref "R9") (pin "1") (pinfunction "1_1") (pintype "passive"))
    )
    (net (code "57") (name "Net-(IC1-OSC_IN)") (class "Default")
      (node (ref "C3") (pin "2") (pinfunction "2_2") (pintype "passive"))
      (node (ref "IC1") (pin "5") (pinfunction "OSC_IN_5") (pintype "passive"))
      (node (ref "crystal1") (pin "1") (pinfunction "1_1") (pintype "passive"))
    )
    (net (code "58") (name "Net-(IC1-OSC_OUT)") (class "Default")
      (node (ref "C4") (pin "2") (pinfunction "2_2") (pintype "passive"))
      (node (ref "IC1") (pin "6") (pinfunction "OSC_OUT_6") (pintype "passive"))
      (node (ref "crystal1") (pin "2") (pinfunction "2_2") (pintype "passive"))
    )
    (net (code "59") (name "Net-(IC1-PB2)") (class "Default")
      (node (ref "IC1") (pin "28") (pinfunction "PB2_28") (pintype "passive"))
      (node (ref "R13") (pin "1") (pinfunction "1_1") (pintype "passive"))
    )
    (net (code "60") (name "Net-(IC1-PC13-TAMPER-RTC)") (class "Default")
      (node (ref "IC1") (pin "2") (pinfunction "PC13-TAMPER-RTC_2") (pintype "passive"))
      (node (ref "R7") (pin "2") (pinfunction "2_2") (pintype "passive"))
    )
    (net (code "61") (name "Net-(IC5-X1)") (class "Default")
      (node (ref "IC5") (pin "1") (pinfunction "X1_1") (pintype "passive"))
      (node (ref "crystal2") (pin "2") (pinfunction "2_2") (pintype "passive"))
    )
    (net (code "62") (name "Net-(IC5-X2)") (class "Default")
      (node (ref "IC5") (pin "2") (pinfunction "X2_2") (pintype "passive"))
      (node (ref "crystal2") (pin "1") (pinfunction "1_1") (pintype "passive"))
    )
    (net (code "63") (name "Net-(J1-Pad2)") (class "Default")
      (node (ref "J1") (pin "2") (pinfunction "2_2") (pintype "passive"))
      (node (ref "R17") (pin "1") (pinfunction "1_1") (pintype "passive"))
    )
    (net (code "64") (name "Net-(J1-Pad3)") (class "Default")
      (node (ref "J1") (pin "3") (pinfunction "3_3") (pintype "passive"))
      (node (ref "R15") (pin "1") (pinfunction "1_1") (pintype "passive"))
      (node (ref "R18") (pin "1") (pinfunction "1_1") (pintype "passive"))
    )
    (net (code "65") (name "Net-(LED2-C)") (class "Default")
      (node (ref "LED2") (pin "2") (pinfunction "C_2") (pintype "passive"))
      (node (ref "R14") (pin "2") (pinfunction "2_2") (pintype "passive"))
    )
    (net (code "66") (name "Net-(LEDT1-A)") (class "Default")
      (node (ref "LEDT1") (pin "1") (pinfunction "A_1") (pintype "passive"))
      (node (ref "R5") (pin "2") (pinfunction "2_2") (pintype "passive"))
    )
    (net (code "67") (name "Net-(LEDT2-A)") (class "Default")
      (node (ref "LEDT2") (pin "1") (pinfunction "A_1") (pintype "passive"))
      (node (ref "R6") (pin "2") (pinfunction "2_2") (pintype "passive"))
    )
    (net (code "68") (name "Net-(LEDT3-A)") (class "Default")
      (node (ref "LEDT3") (pin "1") (pinfunction "A_1") (pintype "passive"))
      (node (ref "R8") (pin "2") (pinfunction "2_2") (pintype "passive"))
    )
    (net (code "69") (name "Net-(LEDT4-A)") (class "Default")
      (node (ref "LEDT4") (pin "1") (pinfunction "A_1") (pintype "passive"))
      (node (ref "R10") (pin "2") (pinfunction "2_2") (pintype "passive"))
    )
    (net (code "70") (name "Net-(Q1-B)") (class "Default")
      (node (ref "Q1") (pin "2") (pinfunction "B_2") (pintype "passive"))
      (node (ref "R1") (pin "2") (pinfunction "2_2") (pintype "passive"))
    )
    (net (code "71") (name "VBAT") (class "Default")
      (node (ref "C14") (pin "1") (pinfunction "1_1") (pintype "passive"))
      (node (ref "H1") (pin "1") (pinfunction "+_1") (pintype "passive"))
      (node (ref "IC1") (pin "1") (pinfunction "VBAT_1") (pintype "passive"))
      (node (ref "IC5") (pin "3") (pinfunction "VBAT_3") (pintype "passive"))
    )
    (net (code "72") (name "unconnected-(DS1-DB1-Pad8)") (class "Default")
      (node (ref "DS1") (pin "8") (pinfunction "DB1_8") (pintype "passive"))
    )
    (net (code "73") (name "unconnected-(DS1-DB2-Pad9)") (class "Default")
      (node (ref "DS1") (pin "9") (pinfunction "DB2_9") (pintype "passive"))
    )
    (net (code "74") (name "unconnected-(DS1-DB3-Pad10)") (class "Default")
      (node (ref "DS1") (pin "10") (pinfunction "DB3_10") (pintype "passive"))
    )
    (net (code "75") (name "unconnected-(IC1-PA0-WKUP-Pad14)") (class "Default")
      (node (ref "IC1") (pin "14") (pinfunction "PA0-WKUP_14") (pintype "passive"))
    )
    (net (code "76") (name "unconnected-(IC1-PA1-Pad15)") (class "Default")
      (node (ref "IC1") (pin "15") (pinfunction "PA1_15") (pintype "passive"))
    )
    (net (code "77") (name "unconnected-(IC1-PA8-Pad41)") (class "Default")
      (node (ref "IC1") (pin "41") (pinfunction "PA8_41") (pintype "passive"))
    )
    (net (code "78") (name "unconnected-(IC1-PB8-Pad61)") (class "Default")
      (node (ref "IC1") (pin "61") (pinfunction "PB8_61") (pintype "passive"))
    )
    (net (code "79") (name "unconnected-(IC1-PB9-Pad62)") (class "Default")
      (node (ref "IC1") (pin "62") (pinfunction "PB9_62") (pintype "passive"))
    )
    (net (code "80") (name "unconnected-(IC1-PC3-Pad11)") (class "Default")
      (node (ref "IC1") (pin "11") (pinfunction "PC3_11") (pintype "passive"))
    )
    (net (code "81") (name "unconnected-(IC1-PC9-Pad40)") (class "Default")
      (node (ref "IC1") (pin "40") (pinfunction "PC9_40") (pintype "passive"))
    )
    (net (code "82") (name "unconnected-(IC1-PC14-OSC32_IN-Pad3)") (class "Default")
      (node (ref "IC1") (pin "3") (pinfunction "PC14-OSC32_IN_3") (pintype "passive"))
    )
    (net (code "83") (name "unconnected-(IC1-PC15-OSC32_OUT-Pad4)") (class "Default")
      (node (ref "IC1") (pin "4") (pinfunction "PC15-OSC32_OUT_4") (pintype "passive"))
    )
    (net (code "84") (name "unconnected-(IC3-ADJ-Pad3)") (class "Default")
      (node (ref "IC3") (pin "3") (pinfunction "ADJ_3") (pintype "passive"))
    )
    (net (code "85") (name "unconnected-(IC5-SQW{slash}OUT-Pad7)") (class "Default")
      (node (ref "IC5") (pin "7") (pinfunction "SQW/OUT_7") (pintype "passive"))
    )
    (net (code "86") (name "unconnected-(J1-Pad4)") (class "Default")
      (node (ref "J1") (pin "4") (pinfunction "4_4") (pintype "passive"))
    )
  )
)
